# SolarBoard_version_2_0.net
KiCad netlist of a schematic drawn in EAGLE
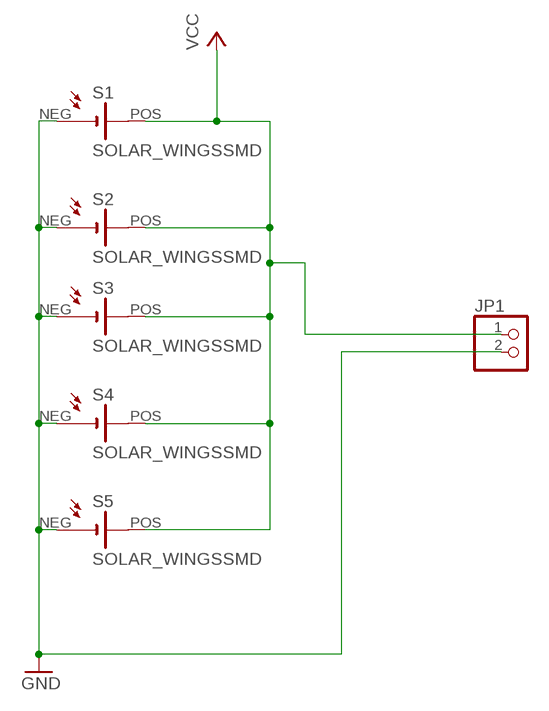
[diagram p0: schematic, sheet 1]

(export (version "E")
  (design (tool "Eeschema 10.0.6"))
  (components
    (comp (ref "JP1")
      (value "PINHD-1X2")
      (footprint "eagle-import:1X02")
      (libsource (lib "eagle-import") (part "PINHD-1X2"))
    )
    (comp (ref "S1")
      (value "SOLAR_WINGSSMD")
      (footprint "eagle-import:SOLAR_WINGS_SMD")
      (libsource (lib "eagle-import") (part "SOLAR_WINGSSMD"))
    )
    (comp (ref "S2")
      (value "SOLAR_WINGSSMD")
      (footprint "eagle-import:SOLAR_WINGS_SMD")
      (libsource (lib "eagle-import") (part "SOLAR_WINGSSMD"))
    )
    (comp (ref "S3")
      (value "SOLAR_WINGSSMD")
      (footprint "eagle-import:SOLAR_WINGS_SMD")
      (libsource (lib "eagle-import") (part "SOLAR_WINGSSMD"))
    )
    (comp (ref "S4")
      (value "SOLAR_WINGSSMD")
      (footprint "eagle-import:SOLAR_WINGS_SMD")
      (libsource (lib "eagle-import") (part "SOLAR_WINGSSMD"))
    )
    (comp (ref "S5")
      (value "SOLAR_WINGSSMD")
      (footprint "eagle-import:SOLAR_WINGS_SMD")
      (libsource (lib "eagle-import") (part "SOLAR_WINGSSMD"))
    )
  )
  (nets
    (net (code "1") (name "GND") (class "Default")
      (node (ref "JP1") (pin "2") (pinfunction "2_2") (pintype "passive"))
      (node (ref "S1") (pin "NEG") (pinfunction "NEG_NEG") (pintype "bidirectional"))
      (node (ref "S2") (pin "NEG") (pinfunction "NEG_NEG") (pintype "bidirectional"))
      (node (ref "S3") (pin "NEG") (pinfunction "NEG_NEG") (pintype "bidirectional"))
      (node (ref "S4") (pin "NEG") (pinfunction "NEG_NEG") (pintype "bidirectional"))
      (node (ref "S5") (pin "NEG") (pinfunction "NEG_NEG") (pintype "bidirectional"))
    )
    (net (code "2") (name "VCC") (class "Default")
      (node (ref "JP1") (pin "1") (pinfunction "1_1") (pintype "passive"))
      (node (ref "S1") (pin "POS") (pinfunction "POS_POS") (pintype "bidirectional"))
      (node (ref "S2") (pin "POS") (pinfunction "POS_POS") (pintype "bidirectional"))
      (node (ref "S3") (pin "POS") (pinfunction "POS_POS") (pintype "bidirectional"))
      (node (ref "S4") (pin "POS") (pinfunction "POS_POS") (pintype "bidirectional"))
      (node (ref "S5") (pin "POS") (pinfunction "POS_POS") (pintype "bidirectional"))
    )
  )
)
